# MiniRS485_RJ45-MySens-v1.net
KiCad netlist of a schematic drawn in EAGLE
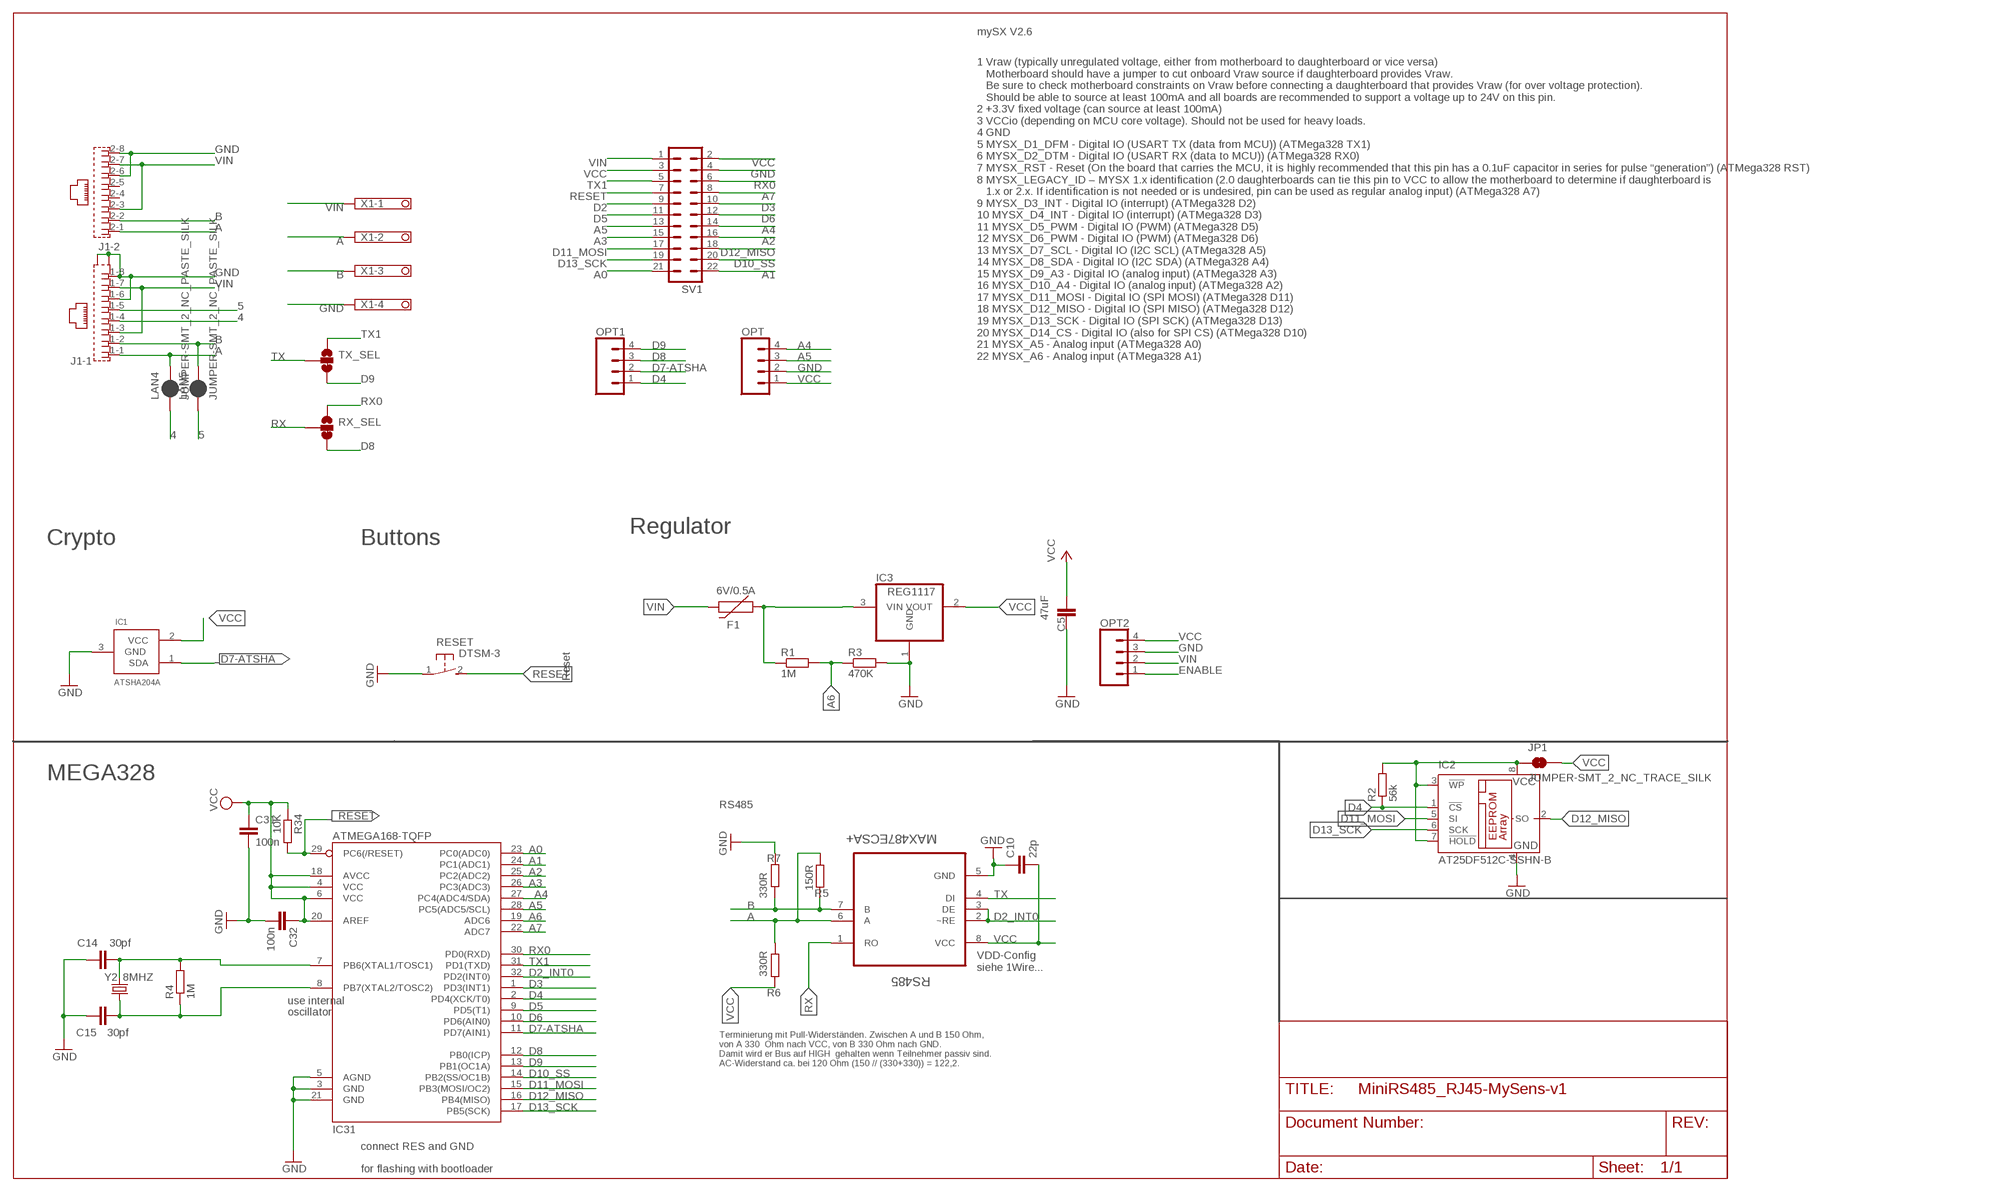
[diagram p0: schematic, sheet 1]

(export (version "E")
  (design (tool "Eeschema 10.0.6"))
  (components
    (comp (ref "C5")
      (value "47uF")
      (footprint "eagle-import:C1210")
      (libsource (lib "eagle-import") (part "C-EUC1210"))
    )
    (comp (ref "C10")
      (value "22p")
      (footprint "eagle-import:C0805")
      (libsource (lib "eagle-import") (part "C-EUC0805"))
    )
    (comp (ref "C14")
      (value "30pf")
      (footprint "eagle-import:C0805")
      (libsource (lib "eagle-import") (part "resistor_348_C-EUC0805"))
    )
    (comp (ref "C15")
      (value "30pf")
      (footprint "eagle-import:C0805")
      (libsource (lib "eagle-import") (part "resistor_348_C-EUC0805"))
    )
    (comp (ref "C31")
      (value "100n")
      (footprint "eagle-import:C0805")
      (libsource (lib "eagle-import") (part "C-EUC0805"))
    )
    (comp (ref "C32")
      (value "100n")
      (footprint "eagle-import:C0805")
      (libsource (lib "eagle-import") (part "C-EUC0805"))
    )
    (comp (ref "F1")
      (value "6V/0.5A")
      (footprint "eagle-import:1206")
      (libsource (lib "eagle-import") (part "PPTC_HALF-AMP"))
    )
    (comp (ref "IC1")
      (value "ATSHA204A")
      (footprint "eagle-import:SOT23")
      (libsource (lib "eagle-import") (part "ATSHA204A"))
    )
    (comp (ref "IC2")
      (value "AT25DF512C-SSHN-B")
      (footprint "eagle-import:SO-08")
      (fields (field (name "MF") "MICROCHIP") (field (name "MPN") "25AA080/SN"))
      (libsource (lib "eagle-import") (part "25SNAA080"))
    )
    (comp (ref "IC3")
      (value "REG1117")
      (footprint "eagle-import:SOT223")
      (libsource (lib "eagle-import") (part "REG1117"))
    )
    (comp (ref "IC31")
      (value "ATMEGA168-TQFP")
      (footprint "eagle-import:TQFP32-08")
      (libsource (lib "eagle-import") (part "ATMEGA168-TQFP"))
    )
    (comp (ref "J1")
      (value "RJ45_2X_NARROW_SHILDPINS_NOCASE")
      (footprint "eagle-import:RJ45_2X_NARROW_SHILDPINS_NOCASE")
      (libsource (lib "eagle-import") (part "RJ45_2X_NARROW_SHILDPINS_NOCASE"))
    )
    (comp (ref "JP1")
      (value "JUMPER-SMT_2_NC_TRACE_SILK")
      (footprint "eagle-import:SMT-JUMPER_2_NC_TRACE_SILK")
      (libsource (lib "eagle-import") (part "JUMPER-SMT_2_NC_TRACE_SILK"))
    )
    (comp (ref "LAN4")
      (value "JUMPER-SMT_2_NC_PASTE_SILK")
      (footprint "eagle-import:SMT-JUMPER_2_NC_PASTE_SILK")
      (libsource (lib "eagle-import") (part "JUMPER-SMT_2_NC_PASTE_SILK"))
    )
    (comp (ref "LAN5")
      (value "JUMPER-SMT_2_NC_PASTE_SILK")
      (footprint "eagle-import:SMT-JUMPER_2_NC_PASTE_SILK")
      (libsource (lib "eagle-import") (part "JUMPER-SMT_2_NC_PASTE_SILK"))
    )
    (comp (ref "OPT")
      (value "CONN_04")
      (footprint "eagle-import:1X04")
      (libsource (lib "eagle-import") (part "CONN_04"))
    )
    (comp (ref "OPT1")
      (value "CONN_04")
      (footprint "eagle-import:1X04")
      (libsource (lib "eagle-import") (part "CONN_04"))
    )
    (comp (ref "OPT2")
      (value "CONN_04")
      (footprint "eagle-import:1X04")
      (libsource (lib "eagle-import") (part "CONN_04"))
    )
    (comp (ref "R1")
      (value "1M")
      (footprint "eagle-import:M0805")
      (libsource (lib "eagle-import") (part "R-EU_M0805"))
    )
    (comp (ref "R2")
      (value "56k")
      (footprint "eagle-import:M0805")
      (libsource (lib "eagle-import") (part "resistor_348_R-EU_M0805"))
    )
    (comp (ref "R3")
      (value "470K")
      (footprint "eagle-import:R0805")
      (libsource (lib "eagle-import") (part "R-EU_R0805"))
    )
    (comp (ref "R4")
      (value "1M")
      (footprint "eagle-import:M0805")
      (libsource (lib "eagle-import") (part "R-EU_M0805"))
    )
    (comp (ref "R5")
      (value "150R")
      (footprint "eagle-import:R0805")
      (libsource (lib "eagle-import") (part "R-EU_R0805"))
    )
    (comp (ref "R6")
      (value "330R")
      (footprint "eagle-import:R0805")
      (libsource (lib "eagle-import") (part "R-EU_R0805"))
    )
    (comp (ref "R7")
      (value "330R")
      (footprint "eagle-import:R0805")
      (libsource (lib "eagle-import") (part "R-EU_R0805"))
    )
    (comp (ref "R34")
      (value "10K")
      (footprint "eagle-import:R0805")
      (libsource (lib "eagle-import") (part "R-EU_R0805"))
    )
    (comp (ref "RESET")
      (value "DTSM-3")
      (footprint "eagle-import:DTSM-3")
      (libsource (lib "eagle-import") (part "DTSM-3"))
    )
    (comp (ref "RS485")
      (value "MAX487ECSA+")
      (footprint "eagle-import:SOIC127P600X175-8N")
      (libsource (lib "eagle-import") (part "MAX487ECSA+"))
    )
    (comp (ref "RX_SEL")
      (value "JUMPER-SMT_3_1-NC_TRACE_SILK")
      (footprint "eagle-import:SMT-JUMPER_3_1-NC_TRACE_SILK")
      (libsource (lib "eagle-import") (part "JUMPER-SMT_3_1-NC_TRACE_SILK"))
    )
    (comp (ref "SV1")
      (value "MA11-2")
      (footprint "eagle-import:MA11-2")
      (libsource (lib "eagle-import") (part "MA11-2"))
    )
    (comp (ref "TX_SEL")
      (value "JUMPER-SMT_3_1-NC_TRACE_SILK")
      (footprint "eagle-import:SMT-JUMPER_3_1-NC_TRACE_SILK")
      (libsource (lib "eagle-import") (part "JUMPER-SMT_3_1-NC_TRACE_SILK"))
    )
    (comp (ref "X1")
      (value "1751264")
      (footprint "eagle-import:1751264")
      (libsource (lib "eagle-import") (part "1751264"))
    )
    (comp (ref "Y2")
      (value "8MHZ")
      (footprint "eagle-import:CRYSTAL-TXC-7A")
      (libsource (lib "eagle-import") (part "CRYSTALTXC-7A"))
    )
  )
  (nets
    (net (code "1") (name "/4") (class "Default")
      (node (ref "J1") (pin "1-4") (pinfunction "4_1-4") (pintype "passive"))
      (node (ref "LAN4") (pin "1") (pinfunction "1_1") (pintype "passive"))
    )
    (net (code "2") (name "/5") (class "Default")
      (node (ref "J1") (pin "1-5") (pinfunction "5_1-5") (pintype "passive"))
      (node (ref "LAN5") (pin "1") (pinfunction "1_1") (pintype "passive"))
    )
    (net (code "3") (name "/A") (class "Default")
      (node (ref "J1") (pin "1-1") (pinfunction "1_1-1") (pintype "passive"))
      (node (ref "J1") (pin "2-1") (pinfunction "1_2-1") (pintype "passive"))
      (node (ref "LAN4") (pin "2") (pinfunction "2_2") (pintype "passive"))
      (node (ref "R5") (pin "1") (pinfunction "1_1") (pintype "passive"))
      (node (ref "R6") (pin "2") (pinfunction "2_2") (pintype "passive"))
      (node (ref "RS485") (pin "6") (pinfunction "A_6") (pintype "bidirectional"))
      (node (ref "X1") (pin "2") (pinfunction "K_2") (pintype "passive"))
    )
    (net (code "4") (name "/A0") (class "Default")
      (node (ref "IC31") (pin "23") (pinfunction "PC0(ADC0)_23") (pintype "bidirectional"))
      (node (ref "SV1") (pin "21") (pinfunction "21_21") (pintype "passive"))
    )
    (net (code "5") (name "/A1") (class "Default")
      (node (ref "IC31") (pin "24") (pinfunction "PC1(ADC1)_24") (pintype "bidirectional"))
      (node (ref "SV1") (pin "22") (pinfunction "22_22") (pintype "passive"))
    )
    (net (code "6") (name "/A2") (class "Default")
      (node (ref "IC31") (pin "25") (pinfunction "PC2(ADC2)_25") (pintype "bidirectional"))
      (node (ref "SV1") (pin "16") (pinfunction "16_16") (pintype "passive"))
    )
    (net (code "7") (name "/A3") (class "Default")
      (node (ref "IC31") (pin "26") (pinfunction "PC3(ADC3)_26") (pintype "bidirectional"))
      (node (ref "SV1") (pin "15") (pinfunction "15_15") (pintype "passive"))
    )
    (net (code "8") (name "/A4") (class "Default")
      (node (ref "IC31") (pin "27") (pinfunction "PC4(ADC4/SDA)_27") (pintype "bidirectional"))
      (node (ref "OPT") (pin "4") (pinfunction "4_4") (pintype "passive"))
      (node (ref "SV1") (pin "14") (pinfunction "14_14") (pintype "passive"))
    )
    (net (code "9") (name "/A5") (class "Default")
      (node (ref "IC31") (pin "28") (pinfunction "PC5(ADC5/SCL)_28") (pintype "bidirectional"))
      (node (ref "OPT") (pin "3") (pinfunction "3_3") (pintype "passive"))
      (node (ref "SV1") (pin "13") (pinfunction "13_13") (pintype "passive"))
    )
    (net (code "10") (name "/A7") (class "Default")
      (node (ref "IC31") (pin "22") (pinfunction "ADC7_22") (pintype "bidirectional"))
      (node (ref "SV1") (pin "8") (pinfunction "8_8") (pintype "passive"))
    )
    (net (code "11") (name "/B") (class "Default")
      (node (ref "J1") (pin "1-2") (pinfunction "2_1-2") (pintype "passive"))
      (node (ref "J1") (pin "2-2") (pinfunction "2_2-2") (pintype "passive"))
      (node (ref "LAN5") (pin "2") (pinfunction "2_2") (pintype "passive"))
      (node (ref "R5") (pin "2") (pinfunction "2_2") (pintype "passive"))
      (node (ref "R7") (pin "1") (pinfunction "1_1") (pintype "passive"))
      (node (ref "RS485") (pin "7") (pinfunction "B_7") (pintype "bidirectional"))
      (node (ref "X1") (pin "3") (pinfunction "K_3") (pintype "passive"))
    )
    (net (code "12") (name "/D2") (class "Default")
      (node (ref "SV1") (pin "9") (pinfunction "9_9") (pintype "passive"))
    )
    (net (code "13") (name "/D2_INT0") (class "Default")
      (node (ref "IC31") (pin "32") (pinfunction "PD2(INT0)_32") (pintype "bidirectional"))
      (node (ref "RS485") (pin "2") (pinfunction "~{RE}_2") (pintype "input"))
      (node (ref "RS485") (pin "3") (pinfunction "DE_3") (pintype "input"))
    )
    (net (code "14") (name "/D3") (class "Default")
      (node (ref "IC31") (pin "1") (pinfunction "PD3(INT1)_1") (pintype "bidirectional"))
      (node (ref "SV1") (pin "10") (pinfunction "10_10") (pintype "passive"))
    )
    (net (code "15") (name "/D5") (class "Default")
      (node (ref "IC31") (pin "9") (pinfunction "PD5(T1)_9") (pintype "bidirectional"))
      (node (ref "SV1") (pin "11") (pinfunction "11_11") (pintype "passive"))
    )
    (net (code "16") (name "/D6") (class "Default")
      (node (ref "IC31") (pin "10") (pinfunction "PD6(AIN0)_10") (pintype "bidirectional"))
      (node (ref "SV1") (pin "12") (pinfunction "12_12") (pintype "passive"))
    )
    (net (code "17") (name "/D7-ATSHA") (class "Default")
      (node (ref "IC1") (pin "1") (pinfunction "SDA_1") (pintype "bidirectional"))
      (node (ref "IC31") (pin "11") (pinfunction "PD7(AIN1)_11") (pintype "bidirectional"))
      (node (ref "OPT1") (pin "2") (pinfunction "2_2") (pintype "passive"))
    )
    (net (code "18") (name "/D8") (class "Default")
      (node (ref "IC31") (pin "12") (pinfunction "PB0(ICP)_12") (pintype "bidirectional"))
      (node (ref "OPT1") (pin "3") (pinfunction "3_3") (pintype "passive"))
      (node (ref "RX_SEL") (pin "3") (pinfunction "3_3") (pintype "passive"))
    )
    (net (code "19") (name "/D9") (class "Default")
      (node (ref "IC31") (pin "13") (pinfunction "PB1(OC1A)_13") (pintype "bidirectional"))
      (node (ref "OPT1") (pin "4") (pinfunction "4_4") (pintype "passive"))
      (node (ref "TX_SEL") (pin "3") (pinfunction "3_3") (pintype "passive"))
    )
    (net (code "20") (name "/D10_SS") (class "Default")
      (node (ref "IC31") (pin "14") (pinfunction "PB2(SS/OC1B)_14") (pintype "bidirectional"))
      (node (ref "SV1") (pin "20") (pinfunction "20_20") (pintype "passive"))
    )
    (net (code "21") (name "/ENABLE") (class "Default")
      (node (ref "OPT2") (pin "1") (pinfunction "1_1") (pintype "passive"))
    )
    (net (code "22") (name "/RX0") (class "Default")
      (node (ref "IC31") (pin "30") (pinfunction "PD0(RXD)_30") (pintype "bidirectional"))
      (node (ref "RX_SEL") (pin "1") (pinfunction "1_1") (pintype "passive"))
      (node (ref "SV1") (pin "6") (pinfunction "6_6") (pintype "passive"))
    )
    (net (code "23") (name "/TX") (class "Default")
      (node (ref "RS485") (pin "4") (pinfunction "DI_4") (pintype "input"))
      (node (ref "TX_SEL") (pin "2") (pinfunction "2_2") (pintype "passive"))
    )
    (net (code "24") (name "/TX1") (class "Default")
      (node (ref "IC31") (pin "31") (pinfunction "PD1(TXD)_31") (pintype "bidirectional"))
      (node (ref "SV1") (pin "5") (pinfunction "5_5") (pintype "passive"))
      (node (ref "TX_SEL") (pin "1") (pinfunction "1_1") (pintype "passive"))
    )
    (net (code "25") (name "A6") (class "Default")
      (node (ref "IC31") (pin "19") (pinfunction "ADC6_19") (pintype "bidirectional"))
      (node (ref "R1") (pin "2") (pinfunction "2_2") (pintype "passive"))
      (node (ref "R3") (pin "1") (pinfunction "1_1") (pintype "passive"))
    )
    (net (code "26") (name "D4") (class "Default")
      (node (ref "IC2") (pin "1") (pinfunction "~{CS}_1") (pintype "input"))
      (node (ref "IC31") (pin "2") (pinfunction "PD4(XCK/T0)_2") (pintype "bidirectional"))
      (node (ref "OPT1") (pin "1") (pinfunction "1_1") (pintype "passive"))
      (node (ref "R2") (pin "1") (pinfunction "1_1") (pintype "passive"))
    )
    (net (code "27") (name "D11_MOSI") (class "Default")
      (node (ref "IC2") (pin "5") (pinfunction "SI_5") (pintype "input"))
      (node (ref "IC31") (pin "15") (pinfunction "PB3(MOSI/OC2)_15") (pintype "bidirectional"))
      (node (ref "SV1") (pin "17") (pinfunction "17_17") (pintype "passive"))
    )
    (net (code "28") (name "D12_MISO") (class "Default")
      (node (ref "IC2") (pin "2") (pinfunction "SO_2") (pintype "bidirectional"))
      (node (ref "IC31") (pin "16") (pinfunction "PB4(MISO)_16") (pintype "bidirectional"))
      (node (ref "SV1") (pin "18") (pinfunction "18_18") (pintype "passive"))
    )
    (net (code "29") (name "D13_SCK") (class "Default")
      (node (ref "IC2") (pin "6") (pinfunction "SCK_6") (pintype "input"))
      (node (ref "IC31") (pin "17") (pinfunction "PB5(SCK)_17") (pintype "bidirectional"))
      (node (ref "SV1") (pin "19") (pinfunction "19_19") (pintype "passive"))
    )
    (net (code "30") (name "GND") (class "Default")
      (node (ref "C10") (pin "1") (pinfunction "1_1") (pintype "passive"))
      (node (ref "C14") (pin "1") (pinfunction "1_1") (pintype "passive"))
      (node (ref "C15") (pin "1") (pinfunction "1_1") (pintype "passive"))
      (node (ref "C31") (pin "2") (pinfunction "2_2") (pintype "passive"))
      (node (ref "C32") (pin "2") (pinfunction "2_2") (pintype "passive"))
      (node (ref "C5") (pin "1") (pinfunction "1_1") (pintype "passive"))
      (node (ref "IC1") (pin "3") (pinfunction "GND_3") (pintype "bidirectional"))
      (node (ref "IC2") (pin "4") (pinfunction "GND_4") (pintype "power_in"))
      (node (ref "IC3") (pin "1") (pinfunction "GND_1") (pintype "power_in"))
      (node (ref "IC31") (pin "21") (pinfunction "GND_21") (pintype "bidirectional"))
      (node (ref "IC31") (pin "3") (pinfunction "GND_3") (pintype "bidirectional"))
      (node (ref "IC31") (pin "5") (pinfunction "AGND_5") (pintype "bidirectional"))
      (node (ref "J1") (pin "1-6") (pinfunction "6_1-6") (pintype "passive"))
      (node (ref "J1") (pin "1-8") (pinfunction "8_1-8") (pintype "passive"))
      (node (ref "J1") (pin "2-6") (pinfunction "6_2-6") (pintype "passive"))
      (node (ref "J1") (pin "2-8") (pinfunction "8_2-8") (pintype "passive"))
      (node (ref "J1") (pin "G1") (pinfunction "S1_G1") (pintype "passive"))
      (node (ref "J1") (pin "G3") (pinfunction "S2_G3") (pintype "passive"))
      (node (ref "OPT") (pin "2") (pinfunction "2_2") (pintype "passive"))
      (node (ref "OPT2") (pin "3") (pinfunction "3_3") (pintype "passive"))
      (node (ref "R3") (pin "2") (pinfunction "2_2") (pintype "passive"))
      (node (ref "R7") (pin "2") (pinfunction "2_2") (pintype "passive"))
      (node (ref "RESET") (pin "1") (pinfunction "1_1") (pintype "passive"))
      (node (ref "RS485") (pin "5") (pinfunction "GND_5") (pintype "passive"))
      (node (ref "SV1") (pin "4") (pinfunction "4_4") (pintype "passive"))
      (node (ref "X1") (pin "4") (pinfunction "K_4") (pintype "passive"))
    )
    (net (code "31") (name "Net-(IC2-VCC)") (class "Default")
      (node (ref "IC2") (pin "3") (pinfunction "~{WP}_3") (pintype "input"))
      (node (ref "IC2") (pin "7") (pinfunction "~{HOLD}_7") (pintype "input"))
      (node (ref "IC2") (pin "8") (pinfunction "VCC_8") (pintype "power_in"))
      (node (ref "JP1") (pin "1") (pinfunction "1_1") (pintype "passive"))
      (node (ref "R2") (pin "2") (pinfunction "2_2") (pintype "passive"))
    )
    (net (code "32") (name "Net-(IC3-VIN)") (class "Default")
      (node (ref "F1") (pin "1") (pinfunction "1_1") (pintype "bidirectional"))
      (node (ref "IC3") (pin "3") (pinfunction "VIN_3") (pintype "input"))
      (node (ref "R1") (pin "1") (pinfunction "1_1") (pintype "passive"))
    )
    (net (code "33") (name "Net-(IC31-PB6(XTAL1{slash}TOSC1))") (class "Default")
      (node (ref "C14") (pin "2") (pinfunction "2_2") (pintype "passive"))
      (node (ref "IC31") (pin "7") (pinfunction "PB6(XTAL1/TOSC1)_7") (pintype "bidirectional"))
      (node (ref "R4") (pin "2") (pinfunction "2_2") (pintype "passive"))
      (node (ref "Y2") (pin "P$2") (pinfunction "2_P$2") (pintype "passive"))
    )
    (net (code "34") (name "Net-(IC31-PB7(XTAL2{slash}TOSC2))") (class "Default")
      (node (ref "C15") (pin "2") (pinfunction "2_2") (pintype "passive"))
      (node (ref "IC31") (pin "8") (pinfunction "PB7(XTAL2/TOSC2)_8") (pintype "bidirectional"))
      (node (ref "R4") (pin "1") (pinfunction "1_1") (pintype "passive"))
      (node (ref "Y2") (pin "P$1") (pinfunction "1_P$1") (pintype "passive"))
    )
    (net (code "35") (name "RESET") (class "Default")
      (node (ref "IC31") (pin "29") (pinfunction "PC6(/RESET)_29") (pintype "bidirectional"))
      (node (ref "R34") (pin "2") (pinfunction "2_2") (pintype "passive"))
      (node (ref "RESET") (pin "2") (pinfunction "2_2") (pintype "passive"))
      (node (ref "SV1") (pin "7") (pinfunction "7_7") (pintype "passive"))
    )
    (net (code "36") (name "RX") (class "Default")
      (node (ref "RS485") (pin "1") (pinfunction "RO_1") (pintype "output"))
      (node (ref "RX_SEL") (pin "2") (pinfunction "2_2") (pintype "passive"))
    )
    (net (code "37") (name "VCC") (class "Default")
      (node (ref "C10") (pin "2") (pinfunction "2_2") (pintype "passive"))
      (node (ref "C31") (pin "1") (pinfunction "1_1") (pintype "passive"))
      (node (ref "C32") (pin "1") (pinfunction "1_1") (pintype "passive"))
      (node (ref "C5") (pin "2") (pinfunction "2_2") (pintype "passive"))
      (node (ref "IC1") (pin "2") (pinfunction "VCC_2") (pintype "bidirectional"))
      (node (ref "IC3") (pin "2") (pinfunction "VOUT_2") (pintype "output"))
      (node (ref "IC31") (pin "18") (pinfunction "AVCC_18") (pintype "bidirectional"))
      (node (ref "IC31") (pin "20") (pinfunction "AREF_20") (pintype "bidirectional"))
      (node (ref "IC31") (pin "4") (pinfunction "VCC_4") (pintype "bidirectional"))
      (node (ref "IC31") (pin "6") (pinfunction "VCC_6") (pintype "bidirectional"))
      (node (ref "JP1") (pin "2") (pinfunction "2_2") (pintype "passive"))
      (node (ref "OPT") (pin "1") (pinfunction "1_1") (pintype "passive"))
      (node (ref "OPT2") (pin "4") (pinfunction "4_4") (pintype "passive"))
      (node (ref "R34") (pin "1") (pinfunction "1_1") (pintype "passive"))
      (node (ref "R6") (pin "1") (pinfunction "1_1") (pintype "passive"))
      (node (ref "RS485") (pin "8") (pinfunction "VCC_8") (pintype "power_in"))
      (node (ref "SV1") (pin "2") (pinfunction "2_2") (pintype "passive"))
      (node (ref "SV1") (pin "3") (pinfunction "3_3") (pintype "passive"))
    )
    (net (code "38") (name "VIN") (class "Default")
      (node (ref "F1") (pin "2") (pinfunction "2_2") (pintype "bidirectional"))
      (node (ref "J1") (pin "1-3") (pinfunction "3_1-3") (pintype "passive"))
      (node (ref "J1") (pin "1-7") (pinfunction "7_1-7") (pintype "passive"))
      (node (ref "J1") (pin "2-3") (pinfunction "3_2-3") (pintype "passive"))
      (node (ref "J1") (pin "2-7") (pinfunction "7_2-7") (pintype "passive"))
      (node (ref "OPT2") (pin "2") (pinfunction "2_2") (pintype "passive"))
      (node (ref "SV1") (pin "1") (pinfunction "1_1") (pintype "passive"))
      (node (ref "X1") (pin "1") (pinfunction "K_1") (pintype "passive"))
    )
    (net (code "39") (name "unconnected-(J1B-4-Pad2-4)") (class "Default")
      (node (ref "J1") (pin "2-4") (pinfunction "4_2-4") (pintype "passive"))
    )
    (net (code "40") (name "unconnected-(J1B-5-Pad2-5)") (class "Default")
      (node (ref "J1") (pin "2-5") (pinfunction "5_2-5") (pintype "passive"))
    )
  )
)
